# E73N.net
KiCad netlist of a schematic drawn in Altium Designer
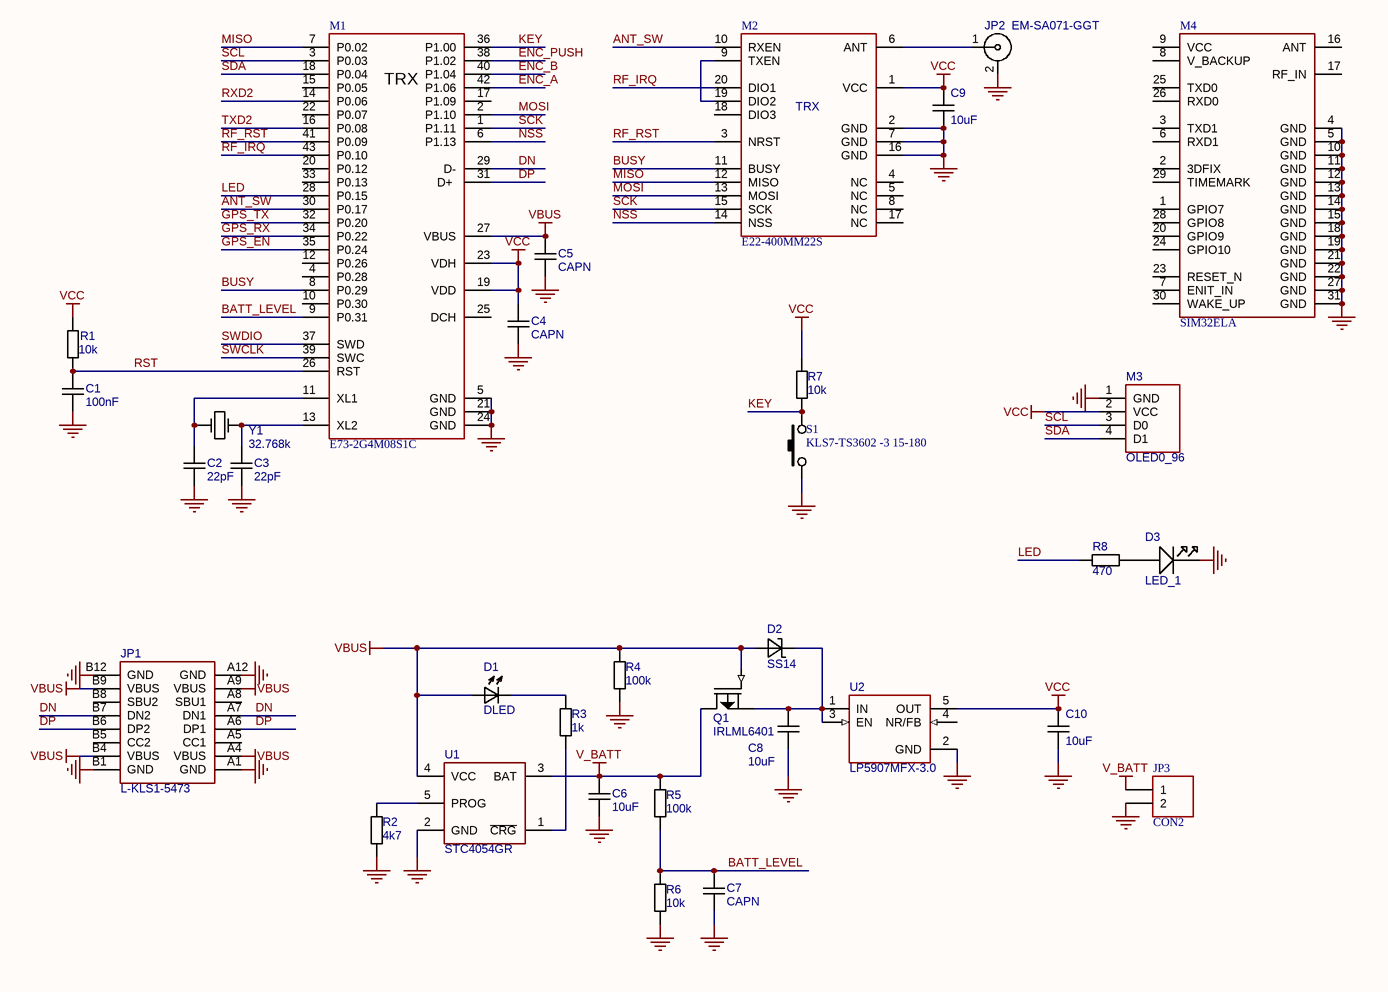
[diagram p0: E73N.SchDoc]

(export (version "E")
  (design (tool "Eeschema 10.0.6"))
  (components
    (comp (ref "C1")
      (value "100nF")
      (footprint "C-0603")
      (fields (field (name "VOLTAGE") "50V"))
      (libsource (lib "Passive") (part "CAPN"))
    )
    (comp (ref "C2")
      (value "22pF")
      (footprint "C-0603")
      (fields (field (name "VOLTAGE") "50V"))
      (libsource (lib "Passive") (part "CAPN"))
    )
    (comp (ref "C3")
      (value "22pF")
      (footprint "C-0603")
      (fields (field (name "VOLTAGE") "50V"))
      (libsource (lib "Passive") (part "CAPN"))
    )
    (comp (ref "C4")
      (value "CAPN")
      (footprint "C-0603")
      (fields (field (name "VOLTAGE") "50V"))
      (libsource (lib "Passive") (part "CAPN"))
    )
    (comp (ref "C5")
      (value "CAPN")
      (footprint "C-0603")
      (fields (field (name "VOLTAGE") "50V"))
      (libsource (lib "Passive") (part "CAPN"))
    )
    (comp (ref "C6")
      (value "10uF")
      (footprint "C-0805")
      (fields (field (name "VOLTAGE") "50V"))
      (libsource (lib "Passive") (part "CAPN"))
    )
    (comp (ref "C7")
      (value "CAPN")
      (footprint "C-0603")
      (fields (field (name "VOLTAGE") "50V"))
      (libsource (lib "Passive") (part "CAPN"))
    )
    (comp (ref "C8")
      (value "10uF")
      (footprint "C-0805")
      (fields (field (name "VOLTAGE") "50V"))
      (libsource (lib "Passive") (part "CAPN"))
    )
    (comp (ref "C9")
      (value "10uF")
      (footprint "C-0805")
      (fields (field (name "VOLTAGE") "50V"))
      (libsource (lib "Passive") (part "CAPN"))
    )
    (comp (ref "C10")
      (value "10uF")
      (footprint "C-0805")
      (fields (field (name "VOLTAGE") "50V"))
      (libsource (lib "Passive") (part "CAPN"))
    )
    (comp (ref "D1") (value "DLED") (footprint "LED_3mm_RED") (libsource (lib "Diodes") (part "DLED")))
    (comp (ref "D2") (value "SS14") (footprint "D-SMA") (libsource (lib "Diodes") (part "DIODSH")))
    (comp (ref "D3") (value "LED_1") (footprint "LED_0805") (libsource (lib "Diodes") (part "LED_1")))
    (comp (ref "JP1")
      (value "L-KLS1-5473")
      (footprint "USB_C_SMD_SLOT")
      (libsource (lib "Connectors") (part "L-KLS1-5473"))
    )
    (comp (ref "JP2")
      (value "EM-SA071-GGT")
      (footprint "SMA_F_EDGE")
      (description "SMA Female R/A PCB Mount")
      (libsource (lib "Connectors") (part "SMA"))
    )
    (comp (ref "JP3") (value "CON2") (footprint "WH-02R") (libsource (lib "Connectors") (part "CON2")))
    (comp (ref "M1")
      (value "E73-2G4M08S1C")
      (footprint "E73-2G4M08S1CX")
      (libsource (lib "RFmodules") (part "E73-2G4M08S1C"))
    )
    (comp (ref "M2")
      (value "E22-400MM22S")
      (footprint "E290-XXXMM20S")
      (libsource (lib "RFmodules") (part "E22-400MM22S"))
    )
    (comp (ref "M3")
      (value "OLED0_96")
      (footprint "OLED096_I2C")
      (libsource (lib "RFmodules") (part "OLED0_96_I2C"))
    )
    (comp (ref "M4")
      (value "SIM32ELA")
      (footprint "LGA_SIM32")
      (libsource (lib "RFmodules") (part "SIM32ELA"))
    )
    (comp (ref "Q1") (value "IRLML6401") (footprint "SOT-23") (libsource (lib "Discrete") (part "MOSF-P")))
    (comp (ref "R1") (value "10k") (footprint "R-0603") (libsource (lib "") (part "RES_2")))
    (comp (ref "R2") (value "4k7") (footprint "R-0603") (libsource (lib "") (part "RES_1")))
    (comp (ref "R3") (value "1k") (footprint "R-0603") (libsource (lib "") (part "RES_2")))
    (comp (ref "R4") (value "100k") (footprint "R-0603") (libsource (lib "") (part "RES_2")))
    (comp (ref "R5") (value "100k") (footprint "R-0603") (libsource (lib "") (part "RES_2")))
    (comp (ref "R6") (value "10k") (footprint "R-0603") (libsource (lib "") (part "RES_2")))
    (comp (ref "R7") (value "10k") (footprint "R-0603") (libsource (lib "Passive") (part "RES")))
    (comp (ref "R8") (value "470") (footprint "R-0603") (libsource (lib "") (part "RES_3")))
    (comp (ref "S1")
      (value "KLS7-TS3602 -3 15-180")
      (footprint "KLS7-TS3602")
      (libsource (lib "Switches") (part "SW-1"))
    )
    (comp (ref "U1") (value "STC4054GR") (footprint "SOT-23-5") (libsource (lib "Power") (part "STC4054")))
    (comp (ref "U2")
      (value "LP5907MFX-3.0")
      (footprint "SOT-23-5")
      (description "250mA Low-Dropout Regulator")
      (libsource (lib "ICs") (part "LP5907"))
    )
    (comp (ref "Y1") (value "32.768k") (footprint "KX-327") (libsource (lib "Passive") (part "Y")))
  )
  (nets
    (net (code "1") (name "/ANT_SW") (class "Default")
      (node (ref "M1") (pin "30") (pinfunction "P0.17_30") (pintype "passive"))
      (node (ref "M2") (pin "10") (pinfunction "RXEN_10") (pintype "passive"))
    )
    (net (code "2") (name "/BATT_LEVEL") (class "Default")
      (node (ref "C7") (pin "1") (pinfunction "1_1") (pintype "passive"))
      (node (ref "M1") (pin "9") (pinfunction "P0.31_9") (pintype "passive"))
      (node (ref "R5") (pin "1") (pinfunction "1_1") (pintype "passive"))
      (node (ref "R6") (pin "2") (pinfunction "2_2") (pintype "passive"))
    )
    (net (code "3") (name "/BUSY") (class "Default")
      (node (ref "M1") (pin "8") (pinfunction "P0.29_8") (pintype "passive"))
      (node (ref "M2") (pin "11") (pinfunction "BUSY_11") (pintype "passive"))
    )
    (net (code "4") (name "/DN") (class "Default")
      (node (ref "JP1") (pin "A7") (pinfunction "DN1_A7") (pintype "passive"))
      (node (ref "JP1") (pin "B7") (pinfunction "DN2_B7") (pintype "passive"))
      (node (ref "M1") (pin "29") (pinfunction "D-_29") (pintype "passive"))
    )
    (net (code "5") (name "/DP") (class "Default")
      (node (ref "JP1") (pin "A6") (pinfunction "DP1_A6") (pintype "passive"))
      (node (ref "JP1") (pin "B6") (pinfunction "DP2_B6") (pintype "passive"))
      (node (ref "M1") (pin "31") (pinfunction "D+_31") (pintype "passive"))
    )
    (net (code "6") (name "/ENC_A") (class "Default")
      (node (ref "M1") (pin "42") (pinfunction "P1.06_42") (pintype "passive"))
    )
    (net (code "7") (name "/ENC_B") (class "Default")
      (node (ref "M1") (pin "40") (pinfunction "P1.04_40") (pintype "passive"))
    )
    (net (code "8") (name "/ENC_PUSH") (class "Default")
      (node (ref "M1") (pin "38") (pinfunction "P1.02_38") (pintype "passive"))
    )
    (net (code "9") (name "/GPS_EN") (class "Default")
      (node (ref "M1") (pin "35") (pinfunction "P0.24_35") (pintype "passive"))
    )
    (net (code "10") (name "/GPS_RX") (class "Default")
      (node (ref "M1") (pin "34") (pinfunction "P0.22_34") (pintype "passive"))
    )
    (net (code "11") (name "/GPS_TX") (class "Default")
      (node (ref "M1") (pin "32") (pinfunction "P0.20_32") (pintype "passive"))
    )
    (net (code "12") (name "/KEY") (class "Default")
      (node (ref "M1") (pin "36") (pinfunction "P1.00_36") (pintype "passive"))
      (node (ref "R7") (pin "2") (pinfunction "2_2") (pintype "passive"))
      (node (ref "S1") (pin "2") (pinfunction "2_2") (pintype "passive"))
    )
    (net (code "13") (name "/LED") (class "Default")
      (node (ref "M1") (pin "28") (pinfunction "P0.15_28") (pintype "passive"))
      (node (ref "R8") (pin "2") (pinfunction "2_2") (pintype "passive"))
    )
    (net (code "14") (name "/MISO") (class "Default")
      (node (ref "M1") (pin "7") (pinfunction "P0.02_7") (pintype "passive"))
      (node (ref "M2") (pin "12") (pinfunction "MISO_12") (pintype "passive"))
    )
    (net (code "15") (name "/MOSI") (class "Default")
      (node (ref "M1") (pin "2") (pinfunction "P1.10_2") (pintype "passive"))
      (node (ref "M2") (pin "13") (pinfunction "MOSI_13") (pintype "passive"))
    )
    (net (code "16") (name "/NSS") (class "Default")
      (node (ref "M1") (pin "6") (pinfunction "P1.13_6") (pintype "passive"))
      (node (ref "M2") (pin "14") (pinfunction "NSS_14") (pintype "passive"))
    )
    (net (code "17") (name "/RF_IRQ") (class "Default")
      (node (ref "M1") (pin "43") (pinfunction "P0.10_43") (pintype "passive"))
      (node (ref "M2") (pin "20") (pinfunction "DIO1_20") (pintype "passive"))
    )
    (net (code "18") (name "/RF_RST") (class "Default")
      (node (ref "M1") (pin "41") (pinfunction "P0.09_41") (pintype "passive"))
      (node (ref "M2") (pin "3") (pinfunction "NRST_3") (pintype "passive"))
    )
    (net (code "19") (name "/RST") (class "Default")
      (node (ref "C1") (pin "2") (pinfunction "2_2") (pintype "passive"))
      (node (ref "M1") (pin "26") (pinfunction "RST_26") (pintype "passive"))
      (node (ref "R1") (pin "1") (pinfunction "1_1") (pintype "passive"))
    )
    (net (code "20") (name "/RXD2") (class "Default")
      (node (ref "M1") (pin "14") (pinfunction "P0.06_14") (pintype "passive"))
    )
    (net (code "21") (name "/SCK") (class "Default")
      (node (ref "M1") (pin "1") (pinfunction "_P1.11_1") (pintype "passive"))
      (node (ref "M2") (pin "15") (pinfunction "SCK_15") (pintype "passive"))
    )
    (net (code "22") (name "/SCL") (class "Default")
      (node (ref "M1") (pin "3") (pinfunction "P0.03_3") (pintype "passive"))
      (node (ref "M3") (pin "3") (pinfunction "D0_3") (pintype "passive"))
    )
    (net (code "23") (name "/SDA") (class "Default")
      (node (ref "M1") (pin "18") (pinfunction "P0.04_18") (pintype "passive"))
      (node (ref "M3") (pin "4") (pinfunction "D1_4") (pintype "passive"))
    )
    (net (code "24") (name "/SWCLK") (class "Default")
      (node (ref "M1") (pin "39") (pinfunction "SWC_39") (pintype "passive"))
    )
    (net (code "25") (name "/SWDIO") (class "Default")
      (node (ref "M1") (pin "37") (pinfunction "SWD_37") (pintype "passive"))
    )
    (net (code "26") (name "/TXD2") (class "Default")
      (node (ref "M1") (pin "16") (pinfunction "P0.08_16") (pintype "passive"))
    )
    (net (code "27") (name "GND") (class "Default")
      (node (ref "C1") (pin "1") (pinfunction "1_1") (pintype "passive"))
      (node (ref "C10") (pin "2") (pinfunction "2_2") (pintype "passive"))
      (node (ref "C2") (pin "1") (pinfunction "1_1") (pintype "passive"))
      (node (ref "C3") (pin "1") (pinfunction "1_1") (pintype "passive"))
      (node (ref "C4") (pin "2") (pinfunction "2_2") (pintype "passive"))
      (node (ref "C5") (pin "2") (pinfunction "2_2") (pintype "passive"))
      (node (ref "C6") (pin "2") (pinfunction "2_2") (pintype "passive"))
      (node (ref "C7") (pin "2") (pinfunction "2_2") (pintype "passive"))
      (node (ref "C8") (pin "2") (pinfunction "2_2") (pintype "passive"))
      (node (ref "C9") (pin "2") (pinfunction "2_2") (pintype "passive"))
      (node (ref "D3") (pin "K") (pinfunction "CATHODE_K") (pintype "passive"))
      (node (ref "JP1") (pin "A1") (pinfunction "GND_A1") (pintype "passive"))
      (node (ref "JP1") (pin "A12") (pinfunction "GND_A12") (pintype "passive"))
      (node (ref "JP1") (pin "B1") (pinfunction "GND_B1") (pintype "passive"))
      (node (ref "JP1") (pin "B12") (pinfunction "GND_B12") (pintype "passive"))
      (node (ref "JP2") (pin "2") (pinfunction "2_2") (pintype "passive"))
      (node (ref "JP3") (pin "2") (pinfunction "2_2") (pintype "passive"))
      (node (ref "M1") (pin "21") (pinfunction "GND_21") (pintype "passive"))
      (node (ref "M1") (pin "24") (pinfunction "GND_24") (pintype "passive"))
      (node (ref "M1") (pin "5") (pinfunction "GND_5") (pintype "passive"))
      (node (ref "M2") (pin "16") (pinfunction "GND_16") (pintype "passive"))
      (node (ref "M2") (pin "2") (pinfunction "GND_2") (pintype "passive"))
      (node (ref "M2") (pin "7") (pinfunction "GND_7") (pintype "passive"))
      (node (ref "M3") (pin "1") (pinfunction "GND_1") (pintype "passive"))
      (node (ref "M4") (pin "10") (pinfunction "GND_10") (pintype "passive"))
      (node (ref "M4") (pin "11") (pinfunction "GND_11") (pintype "passive"))
      (node (ref "M4") (pin "12") (pinfunction "GND_12") (pintype "passive"))
      (node (ref "M4") (pin "13") (pinfunction "GND_13") (pintype "passive"))
      (node (ref "M4") (pin "14") (pinfunction "GND_14") (pintype "passive"))
      (node (ref "M4") (pin "15") (pinfunction "GND_15") (pintype "passive"))
      (node (ref "M4") (pin "18") (pinfunction "GND_18") (pintype "passive"))
      (node (ref "M4") (pin "19") (pinfunction "GND_19") (pintype "passive"))
      (node (ref "M4") (pin "21") (pinfunction "GND_21") (pintype "passive"))
      (node (ref "M4") (pin "22") (pinfunction "GND_22") (pintype "passive"))
      (node (ref "M4") (pin "27") (pinfunction "GND_27") (pintype "passive"))
      (node (ref "M4") (pin "31") (pinfunction "GND_31") (pintype "passive"))
      (node (ref "M4") (pin "4") (pinfunction "GND_4") (pintype "passive"))
      (node (ref "M4") (pin "5") (pinfunction "GND_5") (pintype "passive"))
      (node (ref "R2") (pin "1") (pinfunction "1_1") (pintype "passive"))
      (node (ref "R4") (pin "1") (pinfunction "1_1") (pintype "passive"))
      (node (ref "R6") (pin "1") (pinfunction "1_1") (pintype "passive"))
      (node (ref "S1") (pin "1") (pinfunction "1_1") (pintype "passive"))
      (node (ref "U1") (pin "2") (pinfunction "GND_2") (pintype "passive"))
      (node (ref "U2") (pin "2") (pinfunction "GND_2") (pintype "power_in"))
    )
    (net (code "28") (name "Net-(D1-Pad2)") (class "Default")
      (node (ref "D1") (pin "2") (pinfunction "2_2") (pintype "passive"))
      (node (ref "R3") (pin "2") (pinfunction "2_2") (pintype "passive"))
    )
    (net (code "29") (name "Net-(D3-ANODE)") (class "Default")
      (node (ref "D3") (pin "A") (pinfunction "ANODE_A") (pintype "passive"))
      (node (ref "R8") (pin "1") (pinfunction "1_1") (pintype "passive"))
    )
    (net (code "30") (name "Net-(M1-XL1)") (class "Default")
      (node (ref "C2") (pin "2") (pinfunction "2_2") (pintype "passive"))
      (node (ref "M1") (pin "11") (pinfunction "XL1_11") (pintype "passive"))
      (node (ref "Y1") (pin "2") (pinfunction "2_2") (pintype "passive"))
    )
    (net (code "31") (name "Net-(M1-XL2)") (class "Default")
      (node (ref "C3") (pin "2") (pinfunction "2_2") (pintype "passive"))
      (node (ref "M1") (pin "13") (pinfunction "XL2_13") (pintype "passive"))
      (node (ref "Y1") (pin "1") (pinfunction "1_1") (pintype "passive"))
    )
    (net (code "32") (name "Net-(M2-ANT)") (class "Default")
      (node (ref "JP2") (pin "1") (pinfunction "1_1") (pintype "passive"))
      (node (ref "M2") (pin "6") (pinfunction "ANT_6") (pintype "passive"))
    )
    (net (code "33") (name "Net-(M2-DIO2)") (class "Default")
      (node (ref "M2") (pin "19") (pinfunction "DIO2_19") (pintype "passive"))
      (node (ref "M2") (pin "9") (pinfunction "TXEN_9") (pintype "passive"))
    )
    (net (code "34") (name "Net-(Q1-SOURCE)") (class "Default")
      (node (ref "C8") (pin "1") (pinfunction "1_1") (pintype "passive"))
      (node (ref "D2") (pin "2") (pinfunction "2_2") (pintype "passive"))
      (node (ref "Q1") (pin "2") (pinfunction "SOURCE_2") (pintype "passive"))
      (node (ref "U2") (pin "1") (pinfunction "IN_1") (pintype "power_in"))
      (node (ref "U2") (pin "3") (pinfunction "EN_3") (pintype "input"))
    )
    (net (code "35") (name "Net-(U1-PROG)") (class "Default")
      (node (ref "R2") (pin "2") (pinfunction "2_2") (pintype "passive"))
      (node (ref "U1") (pin "5") (pinfunction "PROG_5") (pintype "passive"))
    )
    (net (code "36") (name "Net-(U1-~{CRG})") (class "Default")
      (node (ref "R3") (pin "1") (pinfunction "1_1") (pintype "passive"))
      (node (ref "U1") (pin "1") (pinfunction "~{CRG}_1") (pintype "passive"))
    )
    (net (code "37") (name "VBUS") (class "Default")
      (node (ref "C5") (pin "1") (pinfunction "1_1") (pintype "passive"))
      (node (ref "D1") (pin "1") (pinfunction "1_1") (pintype "passive"))
      (node (ref "D2") (pin "1") (pinfunction "1_1") (pintype "passive"))
      (node (ref "JP1") (pin "A4") (pinfunction "VBUS_A4") (pintype "passive"))
      (node (ref "JP1") (pin "A9") (pinfunction "VBUS_A9") (pintype "passive"))
      (node (ref "JP1") (pin "B4") (pinfunction "VBUS_B4") (pintype "passive"))
      (node (ref "JP1") (pin "B9") (pinfunction "VBUS_B9") (pintype "passive"))
      (node (ref "M1") (pin "27") (pinfunction "VBUS_27") (pintype "passive"))
      (node (ref "Q1") (pin "1") (pinfunction "GATE_1") (pintype "input"))
      (node (ref "R4") (pin "2") (pinfunction "2_2") (pintype "passive"))
      (node (ref "U1") (pin "4") (pinfunction "VCC_4") (pintype "passive"))
    )
    (net (code "38") (name "VCC") (class "Default")
      (node (ref "C10") (pin "1") (pinfunction "1_1") (pintype "passive"))
      (node (ref "C4") (pin "1") (pinfunction "1_1") (pintype "passive"))
      (node (ref "C9") (pin "1") (pinfunction "1_1") (pintype "passive"))
      (node (ref "M1") (pin "19") (pinfunction "VDD_19") (pintype "passive"))
      (node (ref "M1") (pin "23") (pinfunction "VDH_23") (pintype "passive"))
      (node (ref "M2") (pin "1") (pinfunction "VCC_1") (pintype "passive"))
      (node (ref "M3") (pin "2") (pinfunction "VCC_2") (pintype "passive"))
      (node (ref "R1") (pin "2") (pinfunction "2_2") (pintype "passive"))
      (node (ref "R7") (pin "1") (pinfunction "1_1") (pintype "passive"))
      (node (ref "U2") (pin "5") (pinfunction "OUT_5") (pintype "power_in"))
    )
    (net (code "39") (name "VSS") (class "Default")
      (node (ref "JP1") (pin "17") (pinfunction "VSS_17") (pintype "power_in"))
    )
    (net (code "40") (name "V_BATT") (class "Default")
      (node (ref "C6") (pin "1") (pinfunction "1_1") (pintype "passive"))
      (node (ref "JP3") (pin "1") (pinfunction "1_1") (pintype "passive"))
      (node (ref "Q1") (pin "3") (pinfunction "DRAIN_3") (pintype "passive"))
      (node (ref "R5") (pin "2") (pinfunction "2_2") (pintype "passive"))
      (node (ref "U1") (pin "3") (pinfunction "BAT_3") (pintype "passive"))
    )
    (net (code "41") (name "unconnected-(JP1-CC1-PadA5)") (class "Default")
      (node (ref "JP1") (pin "A5") (pinfunction "CC1_A5") (pintype "passive"))
    )
    (net (code "42") (name "unconnected-(JP1-CC2-PadB5)") (class "Default")
      (node (ref "JP1") (pin "B5") (pinfunction "CC2_B5") (pintype "passive"))
    )
    (net (code "43") (name "unconnected-(JP1-SBU1-PadA8)") (class "Default")
      (node (ref "JP1") (pin "A8") (pinfunction "SBU1_A8") (pintype "passive"))
    )
    (net (code "44") (name "unconnected-(JP1-SBU2-PadB8)") (class "Default")
      (node (ref "JP1") (pin "B8") (pinfunction "SBU2_B8") (pintype "passive"))
    )
    (net (code "45") (name "unconnected-(M1-DCH-Pad25)") (class "Default")
      (node (ref "M1") (pin "25") (pinfunction "DCH_25") (pintype "passive"))
    )
    (net (code "46") (name "unconnected-(M1-P0.05-Pad15)") (class "Default")
      (node (ref "M1") (pin "15") (pinfunction "P0.05_15") (pintype "passive"))
    )
    (net (code "47") (name "unconnected-(M1-P0.07-Pad22)") (class "Default")
      (node (ref "M1") (pin "22") (pinfunction "P0.07_22") (pintype "passive"))
    )
    (net (code "48") (name "unconnected-(M1-P0.12-Pad20)") (class "Default")
      (node (ref "M1") (pin "20") (pinfunction "P0.12_20") (pintype "passive"))
    )
    (net (code "49") (name "unconnected-(M1-P0.13-Pad33)") (class "Default")
      (node (ref "M1") (pin "33") (pinfunction "P0.13_33") (pintype "passive"))
    )
    (net (code "50") (name "unconnected-(M1-P0.26-Pad12)") (class "Default")
      (node (ref "M1") (pin "12") (pinfunction "P0.26_12") (pintype "passive"))
    )
    (net (code "51") (name "unconnected-(M1-P0.28-Pad4)") (class "Default")
      (node (ref "M1") (pin "4") (pinfunction "P0.28_4") (pintype "passive"))
    )
    (net (code "52") (name "unconnected-(M1-P0.30-Pad10)") (class "Default")
      (node (ref "M1") (pin "10") (pinfunction "P0.30_10") (pintype "passive"))
    )
    (net (code "53") (name "unconnected-(M1-P1.09-Pad17)") (class "Default")
      (node (ref "M1") (pin "17") (pinfunction "P1.09_17") (pintype "passive"))
    )
    (net (code "54") (name "unconnected-(M2-DIO3-Pad18)") (class "Default")
      (node (ref "M2") (pin "18") (pinfunction "DIO3_18") (pintype "passive"))
    )
    (net (code "55") (name "unconnected-(M2-NC-Pad4)") (class "Default")
      (node (ref "M2") (pin "4") (pinfunction "NC_4") (pintype "passive"))
    )
    (net (code "56") (name "unconnected-(M2-NC-Pad5)") (class "Default")
      (node (ref "M2") (pin "5") (pinfunction "NC_5") (pintype "passive"))
    )
    (net (code "57") (name "unconnected-(M2-NC-Pad8)") (class "Default")
      (node (ref "M2") (pin "8") (pinfunction "NC_8") (pintype "passive"))
    )
    (net (code "58") (name "unconnected-(M2-NC-Pad17)") (class "Default")
      (node (ref "M2") (pin "17") (pinfunction "NC_17") (pintype "passive"))
    )
    (net (code "59") (name "unconnected-(M4-3DFIX-Pad2)") (class "Default")
      (node (ref "M4") (pin "2") (pinfunction "3DFIX_2") (pintype "passive"))
    )
    (net (code "60") (name "unconnected-(M4-ANT-Pad16)") (class "Default")
      (node (ref "M4") (pin "16") (pinfunction "ANT_16") (pintype "passive"))
    )
    (net (code "61") (name "unconnected-(M4-ENIT_IN-Pad7)") (class "Default")
      (node (ref "M4") (pin "7") (pinfunction "ENIT_IN_7") (pintype "passive"))
    )
    (net (code "62") (name "unconnected-(M4-GPIO7-Pad1)") (class "Default")
      (node (ref "M4") (pin "1") (pinfunction "GPIO7_1") (pintype "passive"))
    )
    (net (code "63") (name "unconnected-(M4-GPIO8-Pad28)") (class "Default")
      (node (ref "M4") (pin "28") (pinfunction "GPIO8_28") (pintype "passive"))
    )
    (net (code "64") (name "unconnected-(M4-GPIO9-Pad20)") (class "Default")
      (node (ref "M4") (pin "20") (pinfunction "GPIO9_20") (pintype "passive"))
    )
    (net (code "65") (name "unconnected-(M4-GPIO10-Pad24)") (class "Default")
      (node (ref "M4") (pin "24") (pinfunction "GPIO10_24") (pintype "passive"))
    )
    (net (code "66") (name "unconnected-(M4-RESET_N-Pad23)") (class "Default")
      (node (ref "M4") (pin "23") (pinfunction "RESET_N_23") (pintype "passive"))
    )
    (net (code "67") (name "unconnected-(M4-RF_IN-Pad17)") (class "Default")
      (node (ref "M4") (pin "17") (pinfunction "RF_IN_17") (pintype "passive"))
    )
    (net (code "68") (name "unconnected-(M4-RXD0-Pad26)") (class "Default")
      (node (ref "M4") (pin "26") (pinfunction "RXD0_26") (pintype "passive"))
    )
    (net (code "69") (name "unconnected-(M4-RXD1-Pad6)") (class "Default")
      (node (ref "M4") (pin "6") (pinfunction "RXD1_6") (pintype "passive"))
    )
    (net (code "70") (name "unconnected-(M4-TIMEMARK-Pad29)") (class "Default")
      (node (ref "M4") (pin "29") (pinfunction "TIMEMARK_29") (pintype "passive"))
    )
    (net (code "71") (name "unconnected-(M4-TXD0-Pad25)") (class "Default")
      (node (ref "M4") (pin "25") (pinfunction "TXD0_25") (pintype "passive"))
    )
    (net (code "72") (name "unconnected-(M4-TXD1-Pad3)") (class "Default")
      (node (ref "M4") (pin "3") (pinfunction "TXD1_3") (pintype "passive"))
    )
    (net (code "73") (name "unconnected-(M4-VCC-Pad9)") (class "Default")
      (node (ref "M4") (pin "9") (pinfunction "VCC_9") (pintype "passive"))
    )
    (net (code "74") (name "unconnected-(M4-V_BACKUP-Pad8)") (class "Default")
      (node (ref "M4") (pin "8") (pinfunction "V_BACKUP_8") (pintype "passive"))
    )
    (net (code "75") (name "unconnected-(M4-WAKE_UP-Pad30)") (class "Default")
      (node (ref "M4") (pin "30") (pinfunction "WAKE_UP_30") (pintype "passive"))
    )
    (net (code "76") (name "unconnected-(U2-NR{slash}FB-Pad4)") (class "Default")
      (node (ref "U2") (pin "4") (pinfunction "NR/FB_4") (pintype "input"))
    )
  )
)
